# DCMv3.net
KiCad netlist of a schematic drawn in EAGLE
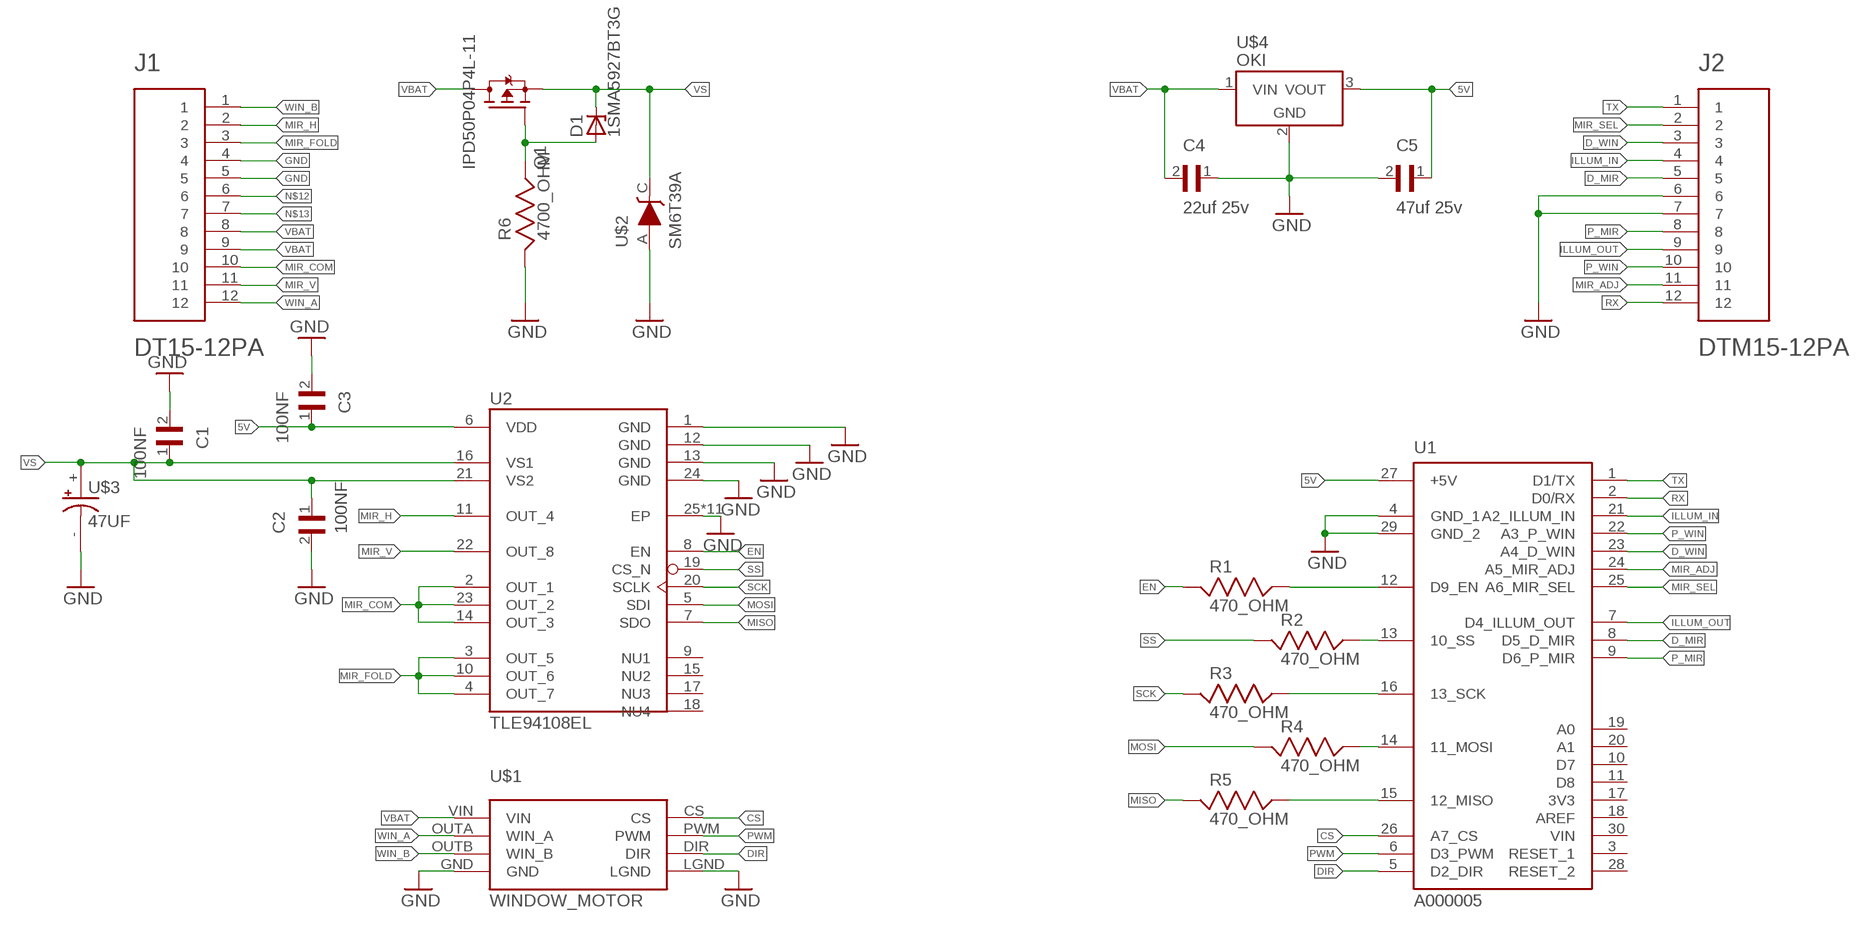
[diagram p0: schematic, sheet 1]

(export (version "E")
  (design (tool "Eeschema 10.0.6"))
  (components
    (comp (ref "C1")
      (value "100NF")
      (footprint "eagle-import:CAPC3216X110N")
      (fields (field (name "MF") "KEMET") (field (name "MP") "C1206C104J5RACTU"))
      (libsource (lib "eagle-import") (part "100NF"))
    )
    (comp (ref "C2")
      (value "100NF")
      (footprint "eagle-import:CAPC3216X110N")
      (fields (field (name "MF") "KEMET") (field (name "MP") "C1206C104J5RACTU"))
      (libsource (lib "eagle-import") (part "100NF"))
    )
    (comp (ref "C3")
      (value "100NF")
      (footprint "eagle-import:CAPC3216X110N")
      (fields (field (name "MF") "KEMET") (field (name "MP") "C1206C104J5RACTU"))
      (libsource (lib "eagle-import") (part "100NF"))
    )
    (comp (ref "C4")
      (value "22uf 25v")
      (footprint "eagle-import:CAP3216X125N")
      (fields (field (name "MF") "Murata Electronics") (field (name "MP") "GRM31CC81E226KE11L"))
      (libsource (lib "eagle-import") (part "GRM31CC81E226KE11L"))
    )
    (comp (ref "C5")
      (value "47uf 25v")
      (footprint "eagle-import:CAP3216X125N")
      (fields (field (name "MF") "Murata Electronics") (field (name "MP") "GRM31CC81E226KE11L"))
      (libsource (lib "eagle-import") (part "GRM31CC81E226KE11L"))
    )
    (comp (ref "D1")
      (value "1SMA5927BT3G")
      (footprint "eagle-import:DO214AC")
      (fields (field (name "MF") "ON Semiconductor"))
      (libsource (lib "eagle-import") (part "1SMA59BT3G27"))
    )
    (comp (ref "J1")
      (value "DT15-12PA")
      (footprint "eagle-import:TE_DT15-12PA")
      (fields (field (name "MF") "TE Connectivity"))
      (libsource (lib "eagle-import") (part "DT15-12PA"))
    )
    (comp (ref "J2")
      (value "DTM15-12PA")
      (footprint "eagle-import:TE_DTM15-12PA")
      (fields (field (name "MF") "TE Connectivity") (field (name "MPN") "DTM15-12PA "))
      (libsource (lib "eagle-import") (part "DTM15-12PA"))
    )
    (comp (ref "Q1")
      (value "IPD50P04P4L-11")
      (footprint "eagle-import:DPAK228P998X235-3N")
      (fields (field (name "MF") "Infineon Technologies"))
      (libsource (lib "eagle-import") (part "IPD50P04P4L-11"))
    )
    (comp (ref "R1")
      (value "470_OHM")
      (footprint "eagle-import:RESC3216X65")
      (fields (field (name "MF") "Yageo") (field (name "MP") "RC1206FR-13470RL"))
      (libsource (lib "eagle-import") (part "470_OHM"))
    )
    (comp (ref "R2")
      (value "470_OHM")
      (footprint "eagle-import:RESC3216X65")
      (fields (field (name "MF") "Yageo") (field (name "MP") "RC1206FR-13470RL"))
      (libsource (lib "eagle-import") (part "470_OHM"))
    )
    (comp (ref "R3")
      (value "470_OHM")
      (footprint "eagle-import:RESC3216X65")
      (fields (field (name "MF") "Yageo") (field (name "MP") "RC1206FR-13470RL"))
      (libsource (lib "eagle-import") (part "470_OHM"))
    )
    (comp (ref "R4")
      (value "470_OHM")
      (footprint "eagle-import:RESC3216X65")
      (fields (field (name "MF") "Yageo") (field (name "MP") "RC1206FR-13470RL"))
      (libsource (lib "eagle-import") (part "470_OHM"))
    )
    (comp (ref "R5")
      (value "470_OHM")
      (footprint "eagle-import:RESC3216X65")
      (fields (field (name "MF") "Yageo") (field (name "MP") "RC1206FR-13470RL"))
      (libsource (lib "eagle-import") (part "470_OHM"))
    )
    (comp (ref "R6")
      (value "4700_OHM")
      (footprint "eagle-import:RESC3216X70")
      (fields (field (name "MF") "Panasonic Electronic") (field (name "MP") "ERJ-8ENF4701V"))
      (libsource (lib "eagle-import") (part "4700_OHM"))
    )
    (comp (ref "U$1")
      (value "WINDOW_MOTOR")
      (footprint "eagle-import:POLOLU")
      (libsource (lib "eagle-import") (part "WINDOW_MOTOR"))
    )
    (comp (ref "U$2")
      (value "SM6T39A")
      (footprint "eagle-import:SM6T39A")
      (libsource (lib "eagle-import") (part "SM6T39A"))
    )
    (comp (ref "U$3")
      (value "47UF")
      (footprint "eagle-import:CAPAE1030X1200")
      (fields (field (name "MF") "Panasonic") (field (name "MP") "EEE-FC1C471AP"))
      (libsource (lib "eagle-import") (part "47UF"))
    )
    (comp (ref "U$4")
      (value "OKI")
      (footprint "eagle-import:OKI-78SR-H")
      (libsource (lib "eagle-import") (part "OKI"))
    )
    (comp (ref "U1")
      (value "A000005")
      (footprint "eagle-import:ARDUINO_A000005")
      (fields (field (name "MF") "Arduino"))
      (libsource (lib "eagle-import") (part "A000005"))
    )
    (comp (ref "U2")
      (value "TLE94108EL")
      (footprint "eagle-import:SOP65P600X170-25N")
      (libsource (lib "eagle-import") (part "TLE94108EL"))
    )
  )
  (nets
    (net (code "1") (name "5V") (class "Default")
      (node (ref "C3") (pin "1") (pinfunction "1_1") (pintype "passive"))
      (node (ref "C5") (pin "1") (pinfunction "1_1") (pintype "passive"))
      (node (ref "U$4") (pin "3") (pinfunction "VOUT_3") (pintype "power_in"))
      (node (ref "U1") (pin "27") (pinfunction "+5V_27") (pintype "power_in"))
      (node (ref "U2") (pin "6") (pinfunction "VDD_6") (pintype "power_in"))
    )
    (net (code "2") (name "CS") (class "Default")
      (node (ref "U$1") (pin "CS") (pinfunction "CS_CS") (pintype "output"))
      (node (ref "U1") (pin "26") (pinfunction "A7_CS_26") (pintype "input"))
    )
    (net (code "3") (name "DIR") (class "Default")
      (node (ref "U$1") (pin "DIR") (pinfunction "DIR_DIR") (pintype "input"))
      (node (ref "U1") (pin "5") (pinfunction "D2_DIR_5") (pintype "output"))
    )
    (net (code "4") (name "D_MIR") (class "Default")
      (node (ref "J2") (pin "5") (pinfunction "5_5") (pintype "passive"))
      (node (ref "U1") (pin "8") (pinfunction "D5_D_MIR_8") (pintype "output"))
    )
    (net (code "5") (name "D_WIN") (class "Default")
      (node (ref "J2") (pin "3") (pinfunction "3_3") (pintype "passive"))
      (node (ref "U1") (pin "23") (pinfunction "A4_D_WIN_23") (pintype "input"))
    )
    (net (code "6") (name "EN") (class "Default")
      (node (ref "R1") (pin "1") (pinfunction "1_1") (pintype "passive"))
      (node (ref "U2") (pin "8") (pinfunction "EN_8") (pintype "input"))
    )
    (net (code "7") (name "GND") (class "Default")
      (node (ref "C1") (pin "2") (pinfunction "2_2") (pintype "passive"))
      (node (ref "C2") (pin "2") (pinfunction "2_2") (pintype "passive"))
      (node (ref "C3") (pin "2") (pinfunction "2_2") (pintype "passive"))
      (node (ref "C4") (pin "1") (pinfunction "1_1") (pintype "passive"))
      (node (ref "C5") (pin "2") (pinfunction "2_2") (pintype "passive"))
      (node (ref "J1") (pin "4") (pinfunction "4_4") (pintype "passive"))
      (node (ref "J1") (pin "5") (pinfunction "5_5") (pintype "passive"))
      (node (ref "J2") (pin "6") (pinfunction "6_6") (pintype "passive"))
      (node (ref "J2") (pin "7") (pinfunction "7_7") (pintype "passive"))
      (node (ref "R6") (pin "1") (pinfunction "1_1") (pintype "passive"))
      (node (ref "U$1") (pin "GND") (pinfunction "GND_GND") (pintype "power_in"))
      (node (ref "U$1") (pin "LGND") (pinfunction "LGND_LGND") (pintype "power_in"))
      (node (ref "U$2") (pin "A") (pinfunction "A_A") (pintype "passive"))
      (node (ref "U$3") (pin "-") (pinfunction "-_-") (pintype "passive"))
      (node (ref "U$4") (pin "2") (pinfunction "GND_2") (pintype "power_in"))
      (node (ref "U1") (pin "29") (pinfunction "GND_2_29") (pintype "power_in"))
      (node (ref "U1") (pin "4") (pinfunction "GND_1_4") (pintype "power_in"))
      (node (ref "U2") (pin "1") (pinfunction "GND_1") (pintype "power_in"))
      (node (ref "U2") (pin "12") (pinfunction "GND_12") (pintype "power_in"))
      (node (ref "U2") (pin "13") (pinfunction "GND_13") (pintype "power_in"))
      (node (ref "U2") (pin "24") (pinfunction "GND_24") (pintype "power_in"))
      (node (ref "U2") (pin "25") (pinfunction "EP_25") (pintype "power_in"))
      (node (ref "U2") (pin "GND") (pinfunction "EP_GND") (pintype "power_in"))
      (node (ref "U2") (pin "GND1") (pinfunction "EP_GND1") (pintype "power_in"))
      (node (ref "U2") (pin "GND2") (pinfunction "EP_GND2") (pintype "power_in"))
      (node (ref "U2") (pin "GND3") (pinfunction "EP_GND3") (pintype "power_in"))
      (node (ref "U2") (pin "GND4") (pinfunction "EP_GND4") (pintype "power_in"))
      (node (ref "U2") (pin "GND5") (pinfunction "EP_GND5") (pintype "power_in"))
      (node (ref "U2") (pin "GND6") (pinfunction "EP_GND6") (pintype "power_in"))
      (node (ref "U2") (pin "GND7") (pinfunction "EP_GND7") (pintype "power_in"))
      (node (ref "U2") (pin "GND8") (pinfunction "EP_GND8") (pintype "power_in"))
      (node (ref "U2") (pin "GND9") (pinfunction "EP_GND9") (pintype "power_in"))
    )
    (net (code "8") (name "ILLUM_IN") (class "Default")
      (node (ref "J2") (pin "4") (pinfunction "4_4") (pintype "passive"))
      (node (ref "U1") (pin "21") (pinfunction "A2_ILLUM_IN_21") (pintype "passive"))
    )
    (net (code "9") (name "ILLUM_OUT") (class "Default")
      (node (ref "J2") (pin "9") (pinfunction "9_9") (pintype "passive"))
      (node (ref "U1") (pin "7") (pinfunction "D4_ILLUM_OUT_7") (pintype "output"))
    )
    (net (code "10") (name "MIR_ADJ") (class "Default")
      (node (ref "J2") (pin "11") (pinfunction "11_11") (pintype "passive"))
      (node (ref "U1") (pin "24") (pinfunction "A5_MIR_ADJ_24") (pintype "input"))
    )
    (net (code "11") (name "MIR_COM") (class "Default")
      (node (ref "J1") (pin "10") (pinfunction "10_10") (pintype "passive"))
      (node (ref "U2") (pin "14") (pinfunction "OUT_3_14") (pintype "bidirectional"))
      (node (ref "U2") (pin "2") (pinfunction "OUT_1_2") (pintype "bidirectional"))
      (node (ref "U2") (pin "23") (pinfunction "OUT_2_23") (pintype "bidirectional"))
    )
    (net (code "12") (name "MIR_FOLD") (class "Default")
      (node (ref "J1") (pin "3") (pinfunction "3_3") (pintype "passive"))
      (node (ref "U2") (pin "10") (pinfunction "OUT_6_10") (pintype "bidirectional"))
      (node (ref "U2") (pin "3") (pinfunction "OUT_5_3") (pintype "bidirectional"))
      (node (ref "U2") (pin "4") (pinfunction "OUT_7_4") (pintype "bidirectional"))
    )
    (net (code "13") (name "MIR_H") (class "Default")
      (node (ref "J1") (pin "2") (pinfunction "2_2") (pintype "passive"))
      (node (ref "U2") (pin "11") (pinfunction "OUT_4_11") (pintype "bidirectional"))
    )
    (net (code "14") (name "MIR_SEL") (class "Default")
      (node (ref "J2") (pin "2") (pinfunction "2_2") (pintype "passive"))
      (node (ref "U1") (pin "25") (pinfunction "A6_MIR_SEL_25") (pintype "input"))
    )
    (net (code "15") (name "MIR_V") (class "Default")
      (node (ref "J1") (pin "11") (pinfunction "11_11") (pintype "passive"))
      (node (ref "U2") (pin "22") (pinfunction "OUT_8_22") (pintype "bidirectional"))
    )
    (net (code "16") (name "MISO") (class "Default")
      (node (ref "R5") (pin "1") (pinfunction "1_1") (pintype "passive"))
      (node (ref "U2") (pin "7") (pinfunction "SDO_7") (pintype "output"))
    )
    (net (code "17") (name "MOSI") (class "Default")
      (node (ref "R4") (pin "1") (pinfunction "1_1") (pintype "passive"))
      (node (ref "U2") (pin "5") (pinfunction "SDI_5") (pintype "input"))
    )
    (net (code "18") (name "N$12") (class "Default")
      (node (ref "J1") (pin "6") (pinfunction "6_6") (pintype "passive"))
    )
    (net (code "19") (name "N$13") (class "Default")
      (node (ref "J1") (pin "7") (pinfunction "7_7") (pintype "passive"))
    )
    (net (code "20") (name "Net-(Q1-G)") (class "Default")
      (node (ref "D1") (pin "A") (pinfunction "A_A") (pintype "passive"))
      (node (ref "Q1") (pin "1") (pinfunction "G_1") (pintype "passive"))
      (node (ref "R6") (pin "2") (pinfunction "2_2") (pintype "passive"))
    )
    (net (code "21") (name "Net-(U1-10_SS)") (class "Default")
      (node (ref "R2") (pin "2") (pinfunction "2_2") (pintype "passive"))
      (node (ref "U1") (pin "13") (pinfunction "10_SS_13") (pintype "output"))
    )
    (net (code "22") (name "Net-(U1-11_MOSI)") (class "Default")
      (node (ref "R4") (pin "2") (pinfunction "2_2") (pintype "passive"))
      (node (ref "U1") (pin "14") (pinfunction "11_MOSI_14") (pintype "output"))
    )
    (net (code "23") (name "Net-(U1-12_MISO)") (class "Default")
      (node (ref "R5") (pin "2") (pinfunction "2_2") (pintype "passive"))
      (node (ref "U1") (pin "15") (pinfunction "12_MISO_15") (pintype "input"))
    )
    (net (code "24") (name "Net-(U1-13_SCK)") (class "Default")
      (node (ref "R3") (pin "2") (pinfunction "2_2") (pintype "passive"))
      (node (ref "U1") (pin "16") (pinfunction "13_SCK_16") (pintype "output"))
    )
    (net (code "25") (name "Net-(U1-D9_EN)") (class "Default")
      (node (ref "R1") (pin "2") (pinfunction "2_2") (pintype "passive"))
      (node (ref "U1") (pin "12") (pinfunction "D9_EN_12") (pintype "output"))
    )
    (net (code "26") (name "PWM") (class "Default")
      (node (ref "U$1") (pin "PWM") (pinfunction "PWM_PWM") (pintype "input"))
      (node (ref "U1") (pin "6") (pinfunction "D3_PWM_6") (pintype "output"))
    )
    (net (code "27") (name "P_MIR") (class "Default")
      (node (ref "J2") (pin "8") (pinfunction "8_8") (pintype "passive"))
      (node (ref "U1") (pin "9") (pinfunction "D6_P_MIR_9") (pintype "output"))
    )
    (net (code "28") (name "P_WIN") (class "Default")
      (node (ref "J2") (pin "10") (pinfunction "10_10") (pintype "passive"))
      (node (ref "U1") (pin "22") (pinfunction "A3_P_WIN_22") (pintype "input"))
    )
    (net (code "29") (name "RX") (class "Default")
      (node (ref "J2") (pin "12") (pinfunction "12_12") (pintype "passive"))
      (node (ref "U1") (pin "2") (pinfunction "D0/RX_2") (pintype "input"))
    )
    (net (code "30") (name "SCK") (class "Default")
      (node (ref "R3") (pin "1") (pinfunction "1_1") (pintype "passive"))
      (node (ref "U2") (pin "20") (pinfunction "SCLK_20") (pintype "input"))
    )
    (net (code "31") (name "SS") (class "Default")
      (node (ref "R2") (pin "1") (pinfunction "1_1") (pintype "passive"))
      (node (ref "U2") (pin "19") (pinfunction "CS_N_19") (pintype "input"))
    )
    (net (code "32") (name "TX") (class "Default")
      (node (ref "J2") (pin "1") (pinfunction "1_1") (pintype "passive"))
      (node (ref "U1") (pin "1") (pinfunction "D1/TX_1") (pintype "output"))
    )
    (net (code "33") (name "VBAT") (class "Default")
      (node (ref "C4") (pin "2") (pinfunction "2_2") (pintype "passive"))
      (node (ref "J1") (pin "8") (pinfunction "8_8") (pintype "passive"))
      (node (ref "J1") (pin "9") (pinfunction "9_9") (pintype "passive"))
      (node (ref "Q1") (pin "2") (pinfunction "D_2") (pintype "passive"))
      (node (ref "U$1") (pin "VIN") (pinfunction "VIN_VIN") (pintype "power_in"))
      (node (ref "U$4") (pin "1") (pinfunction "VIN_1") (pintype "power_in"))
    )
    (net (code "34") (name "VS") (class "Default")
      (node (ref "C1") (pin "1") (pinfunction "1_1") (pintype "passive"))
      (node (ref "C2") (pin "1") (pinfunction "1_1") (pintype "passive"))
      (node (ref "D1") (pin "C") (pinfunction "C_C") (pintype "passive"))
      (node (ref "Q1") (pin "3") (pinfunction "S_3") (pintype "passive"))
      (node (ref "U$2") (pin "C") (pinfunction "C_C") (pintype "passive"))
      (node (ref "U$3") (pin "+") (pinfunction "+_+") (pintype "passive"))
      (node (ref "U2") (pin "16") (pinfunction "VS1_16") (pintype "power_in"))
      (node (ref "U2") (pin "21") (pinfunction "VS2_21") (pintype "power_in"))
    )
    (net (code "35") (name "WIN_A") (class "Default")
      (node (ref "J1") (pin "12") (pinfunction "12_12") (pintype "passive"))
      (node (ref "U$1") (pin "OUTA") (pinfunction "WIN_A_OUTA") (pintype "output"))
    )
    (net (code "36") (name "WIN_B") (class "Default")
      (node (ref "J1") (pin "1") (pinfunction "1_1") (pintype "passive"))
      (node (ref "U$1") (pin "OUTB") (pinfunction "WIN_B_OUTB") (pintype "output"))
    )
    (net (code "37") (name "unconnected-(U1-3V3-Pad17)") (class "Default")
      (node (ref "U1") (pin "17") (pinfunction "3V3_17") (pintype "passive"))
    )
    (net (code "38") (name "unconnected-(U1-A0-Pad19)") (class "Default")
      (node (ref "U1") (pin "19") (pinfunction "A0_19") (pintype "passive"))
    )
    (net (code "39") (name "unconnected-(U1-A1-Pad20)") (class "Default")
      (node (ref "U1") (pin "20") (pinfunction "A1_20") (pintype "passive"))
    )
    (net (code "40") (name "unconnected-(U1-AREF-Pad18)") (class "Default")
      (node (ref "U1") (pin "18") (pinfunction "AREF_18") (pintype "passive"))
    )
    (net (code "41") (name "unconnected-(U1-D7-Pad10)") (class "Default")
      (node (ref "U1") (pin "10") (pinfunction "D7_10") (pintype "output"))
    )
    (net (code "42") (name "unconnected-(U1-D8-Pad11)") (class "Default")
      (node (ref "U1") (pin "11") (pinfunction "D8_11") (pintype "passive"))
    )
    (net (code "43") (name "unconnected-(U1-RESET_1-Pad3)") (class "Default")
      (node (ref "U1") (pin "3") (pinfunction "RESET_1_3") (pintype "passive"))
    )
    (net (code "44") (name "unconnected-(U1-RESET_2-Pad28)") (class "Default")
      (node (ref "U1") (pin "28") (pinfunction "RESET_2_28") (pintype "passive"))
    )
    (net (code "45") (name "unconnected-(U1-VIN-Pad30)") (class "Default")
      (node (ref "U1") (pin "30") (pinfunction "VIN_30") (pintype "passive"))
    )
    (net (code "46") (name "unconnected-(U2-NU1-Pad9)") (class "Default")
      (node (ref "U2") (pin "9") (pinfunction "NU1_9") (pintype "passive"))
    )
    (net (code "47") (name "unconnected-(U2-NU2-Pad15)") (class "Default")
      (node (ref "U2") (pin "15") (pinfunction "NU2_15") (pintype "passive"))
    )
    (net (code "48") (name "unconnected-(U2-NU3-Pad17)") (class "Default")
      (node (ref "U2") (pin "17") (pinfunction "NU3_17") (pintype "passive"))
    )
    (net (code "49") (name "unconnected-(U2-NU4-Pad18)") (class "Default")
      (node (ref "U2") (pin "18") (pinfunction "NU4_18") (pintype "passive"))
    )
  )
)
